# ProPrj_stc8h1k_ESC_2025-05-31.net
KiCad netlist of a schematic drawn in EasyEDA Pro
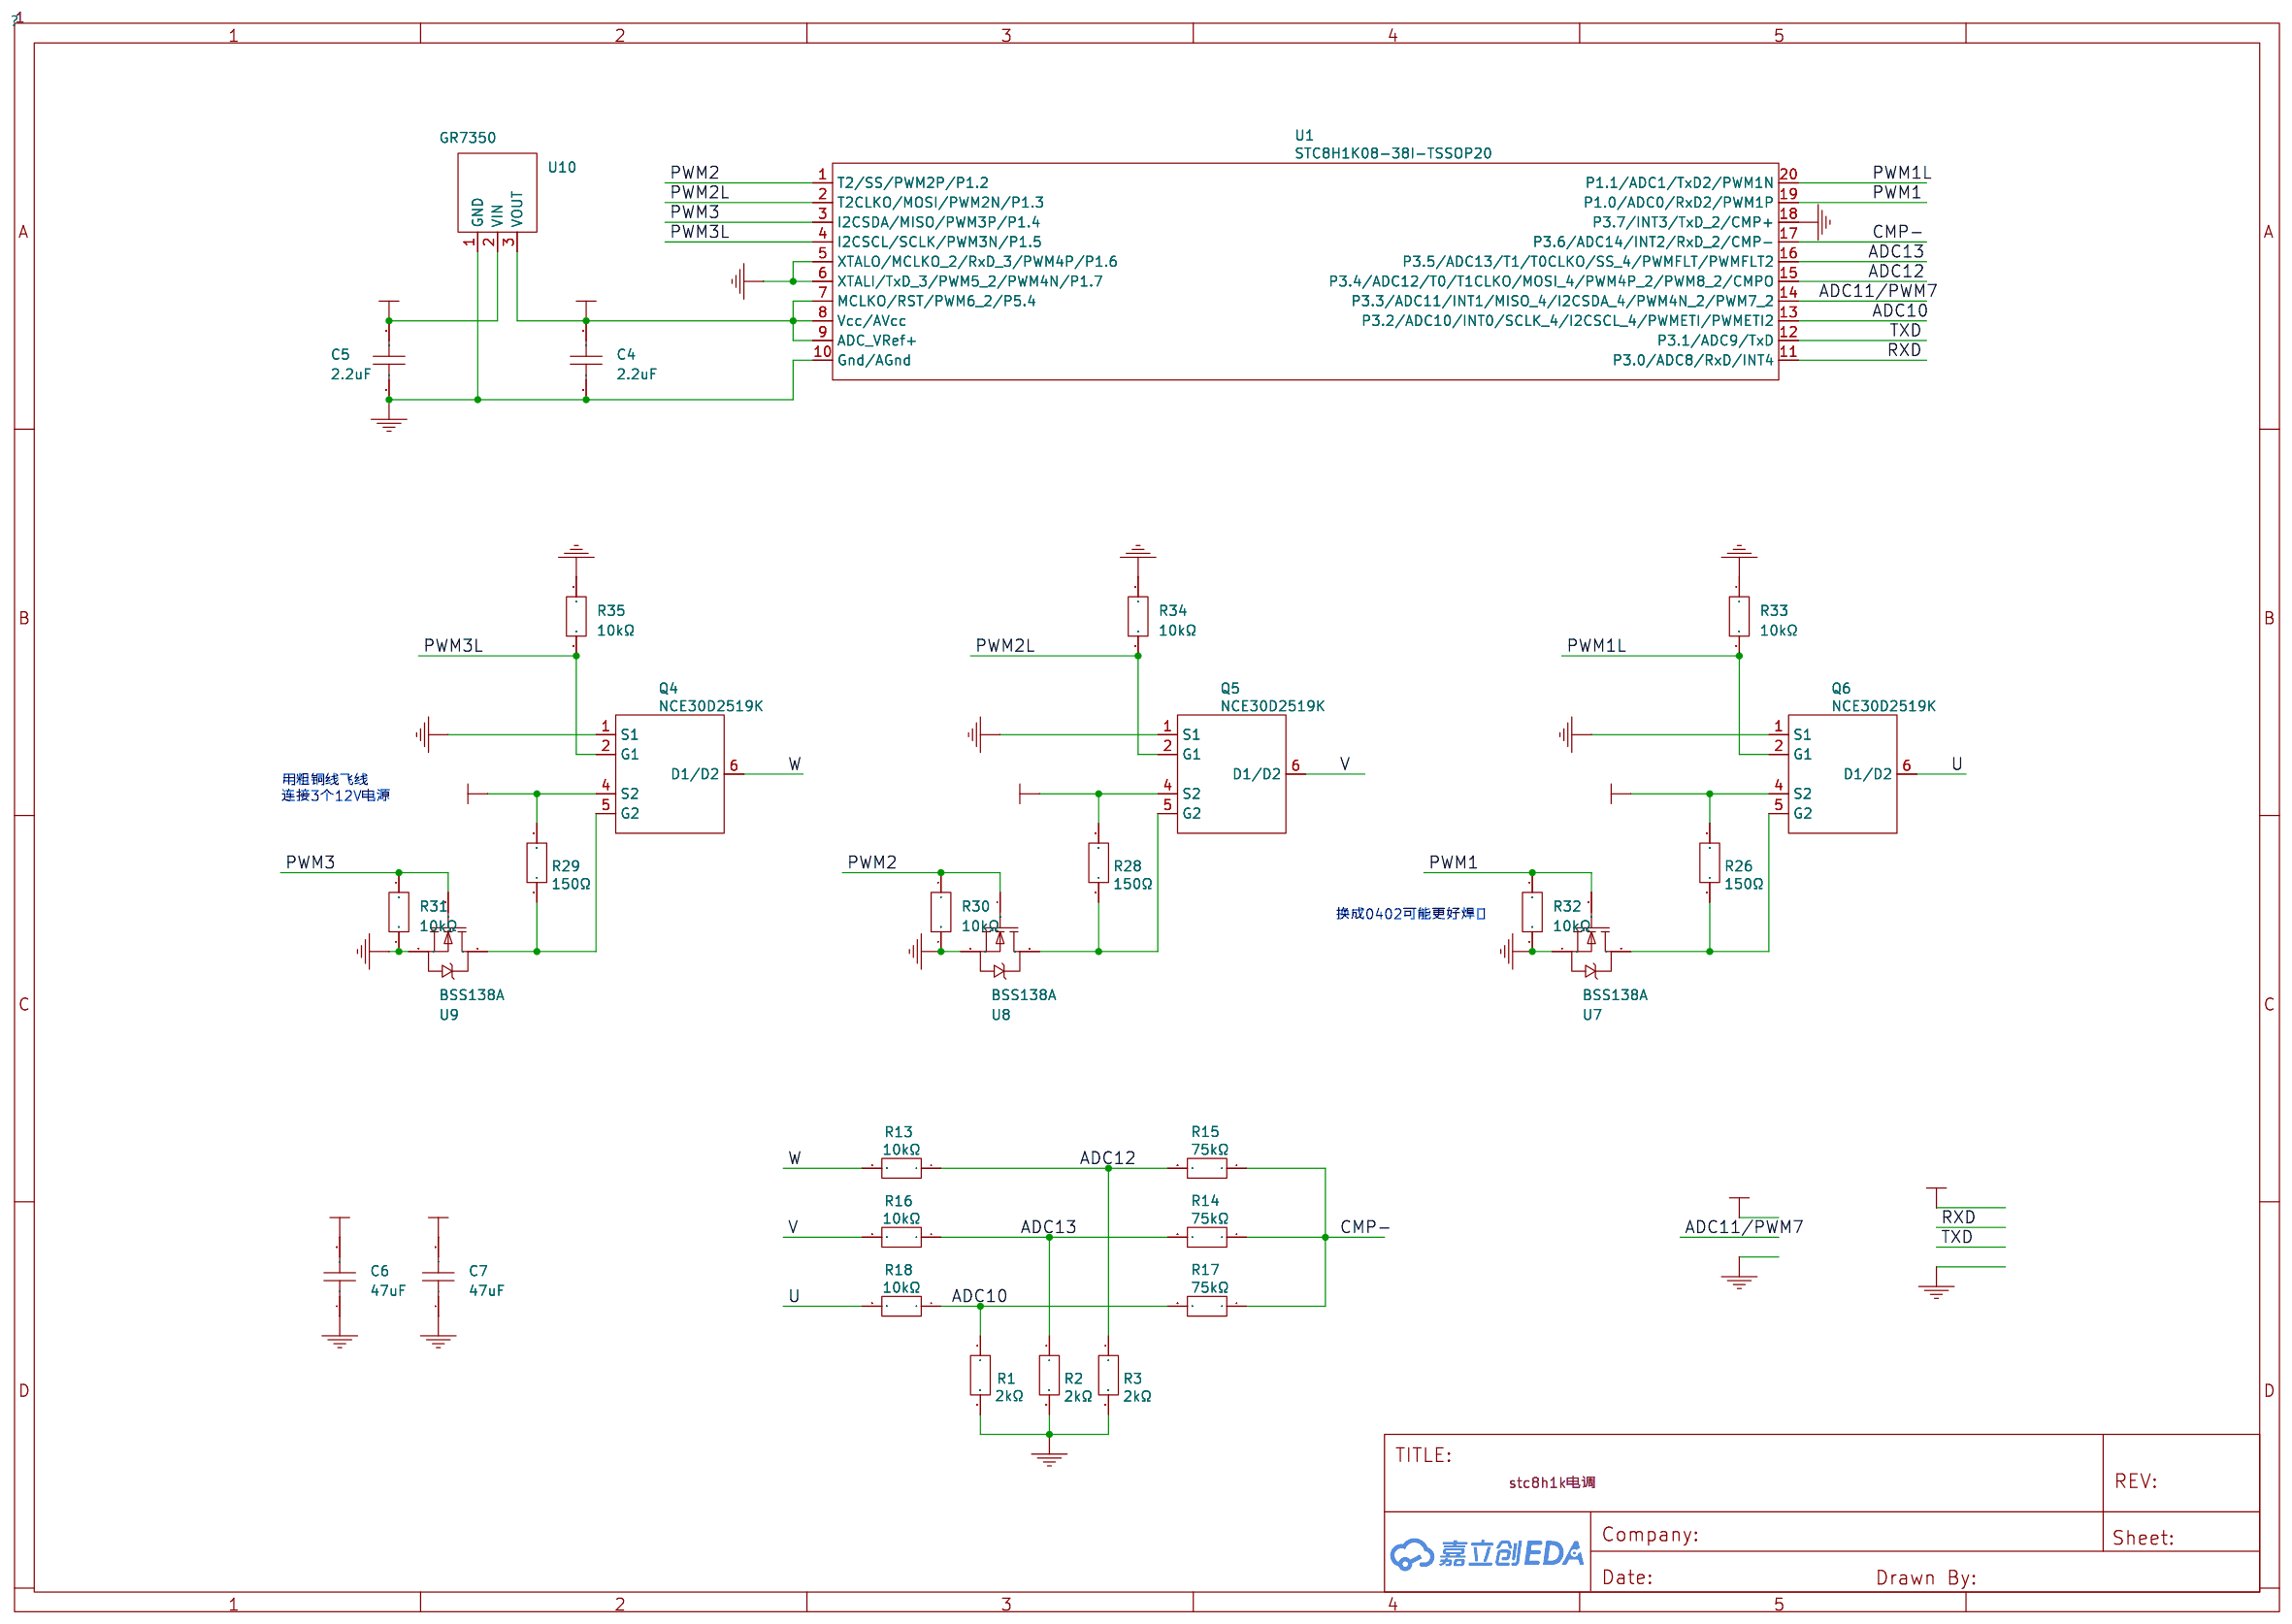
[diagram p0: schematic sheet]

(export (version "E")
  (design (tool "Eeschema 10.0.6"))
  (components
    (comp (ref "C4")
      (value "2.2uF")
      (fields (field (name "Manufacturer Part") "0603B104M250NT") (field (name "Manufacturer") "FH(风华)"))
      (libsource (lib "easyedapro") (part "104"))
    )
    (comp (ref "C5")
      (value "2.2uF")
      (fields (field (name "Manufacturer Part") "0603B104M250NT") (field (name "Manufacturer") "FH(风华)"))
      (libsource (lib "easyedapro") (part "106"))
    )
    (comp (ref "C6")
      (value "47uF")
      (footprint "easyedapro:C1206")
      (description "容值:47uF;精度:±20%;额定电压:25V;材质(温度系数):X5R;")
      (fields
        (field (name "Manufacturer Part") "GRM31CR61E476ME44L")
        (field (name "Manufacturer") "muRata(村田)")
      )
      (libsource (lib "easyedapro") (part "GRM31CR61E476ME44L"))
    )
    (comp (ref "C7")
      (value "47uF")
      (footprint "easyedapro:C1206")
      (description "容值:47uF;精度:±20%;额定电压:25V;材质(温度系数):X5R;")
      (fields
        (field (name "Manufacturer Part") "GRM31CR61E476ME44L")
        (field (name "Manufacturer") "muRata(村田)")
      )
      (libsource (lib "easyedapro") (part "GRM31CR61E476ME44L"))
    )
    (comp (ref "Q4")
      (value "NCE30D2519K")
      (footprint "easyedapro:TO-252-5-11_L6.5-W6.2-P1.14-LS10.0-BR")
      (fields (field (name "Manufacturer") "NCE(无锡新洁能)"))
      (libsource (lib "easyedapro") (part "NCE30D2519K"))
    )
    (comp (ref "Q5")
      (value "NCE30D2519K")
      (footprint "easyedapro:TO-252-5-11_L6.5-W6.2-P1.14-LS10.0-BR")
      (fields (field (name "Manufacturer") "NCE(无锡新洁能)"))
      (libsource (lib "easyedapro") (part "NCE30D2519K"))
    )
    (comp (ref "Q6")
      (value "NCE30D2519K")
      (footprint "easyedapro:TO-252-5-11_L6.5-W6.2-P1.14-LS10.0-BR")
      (fields (field (name "Manufacturer") "NCE(无锡新洁能)"))
      (libsource (lib "easyedapro") (part "NCE30D2519K"))
    )
    (comp (ref "R1")
      (value "2kΩ")
      (fields (field (name "Manufacturer Part") "RC0603FR-1347RL") (field (name "Manufacturer") "YAGEO(国巨)"))
      (libsource (lib "easyedapro") (part "1.5K"))
    )
    (comp (ref "R2")
      (value "2kΩ")
      (fields (field (name "Manufacturer Part") "RC0603FR-1347RL") (field (name "Manufacturer") "YAGEO(国巨)"))
      (libsource (lib "easyedapro") (part "1.5K"))
    )
    (comp (ref "R3")
      (value "2kΩ")
      (fields (field (name "Manufacturer Part") "RC0603FR-1347RL") (field (name "Manufacturer") "YAGEO(国巨)"))
      (libsource (lib "easyedapro") (part "1.5K"))
    )
    (comp (ref "R13")
      (value "10kΩ")
      (fields (field (name "Manufacturer Part") "RC0603FR-1347RL") (field (name "Manufacturer") "YAGEO(国巨)"))
      (libsource (lib "easyedapro") (part "10K"))
    )
    (comp (ref "R14")
      (value "75kΩ")
      (fields (field (name "Manufacturer Part") "RC0603FR-1347RL") (field (name "Manufacturer") "YAGEO(国巨)"))
      (libsource (lib "easyedapro") (part "10K"))
    )
    (comp (ref "R15")
      (value "75kΩ")
      (fields (field (name "Manufacturer Part") "RC0603FR-1347RL") (field (name "Manufacturer") "YAGEO(国巨)"))
      (libsource (lib "easyedapro") (part "10K"))
    )
    (comp (ref "R16")
      (value "10kΩ")
      (fields (field (name "Manufacturer Part") "RC0603FR-1347RL") (field (name "Manufacturer") "YAGEO(国巨)"))
      (libsource (lib "easyedapro") (part "10K"))
    )
    (comp (ref "R17")
      (value "75kΩ")
      (fields (field (name "Manufacturer Part") "RC0603FR-1347RL") (field (name "Manufacturer") "YAGEO(国巨)"))
      (libsource (lib "easyedapro") (part "10K"))
    )
    (comp (ref "R18")
      (value "10kΩ")
      (fields (field (name "Manufacturer Part") "RC0603FR-1347RL") (field (name "Manufacturer") "YAGEO(国巨)"))
      (libsource (lib "easyedapro") (part "10K"))
    )
    (comp (ref "R26")
      (value "150Ω")
      (footprint "easyedapro:R0603")
      (fields (field (name "Manufacturer Part") "RC0603FR-1347RL") (field (name "Manufacturer") "YAGEO(国巨)"))
      (libsource (lib "easyedapro") (part "300R"))
    )
    (comp (ref "R28")
      (value "150Ω")
      (footprint "easyedapro:R0603")
      (fields (field (name "Manufacturer Part") "RC0603FR-1347RL") (field (name "Manufacturer") "YAGEO(国巨)"))
      (libsource (lib "easyedapro") (part "300R"))
    )
    (comp (ref "R29")
      (value "150Ω")
      (footprint "easyedapro:R0603")
      (fields (field (name "Manufacturer Part") "RC0603FR-1347RL") (field (name "Manufacturer") "YAGEO(国巨)"))
      (libsource (lib "easyedapro") (part "300R"))
    )
    (comp (ref "R30")
      (value "10kΩ")
      (fields (field (name "Manufacturer Part") "RC0603FR-1347RL") (field (name "Manufacturer") "YAGEO(国巨)"))
      (libsource (lib "easyedapro") (part "10K"))
    )
    (comp (ref "R31")
      (value "10kΩ")
      (fields (field (name "Manufacturer Part") "RC0603FR-1347RL") (field (name "Manufacturer") "YAGEO(国巨)"))
      (libsource (lib "easyedapro") (part "10K"))
    )
    (comp (ref "R32")
      (value "10kΩ")
      (fields (field (name "Manufacturer Part") "RC0603FR-1347RL") (field (name "Manufacturer") "YAGEO(国巨)"))
      (libsource (lib "easyedapro") (part "10K"))
    )
    (comp (ref "R33")
      (value "10kΩ")
      (fields (field (name "Manufacturer Part") "RC0603FR-1347RL") (field (name "Manufacturer") "YAGEO(国巨)"))
      (libsource (lib "easyedapro") (part "10K"))
    )
    (comp (ref "R34")
      (value "10kΩ")
      (fields (field (name "Manufacturer Part") "RC0603FR-1347RL") (field (name "Manufacturer") "YAGEO(国巨)"))
      (libsource (lib "easyedapro") (part "10K"))
    )
    (comp (ref "R35")
      (value "10kΩ")
      (fields (field (name "Manufacturer Part") "RC0603FR-1347RL") (field (name "Manufacturer") "YAGEO(国巨)"))
      (libsource (lib "easyedapro") (part "10K"))
    )
    (comp (ref "U1")
      (value "STC8H1K08-38I-TSSOP20")
      (libsource (lib "easyedapro") (part "STC8H1K08-38I-TSSOP20"))
    )
    (comp (ref "U7")
      (value "BSS138A")
      (footprint "easyedapro:SOT-23-3_L2.9-W1.6-P1.90-LS2.8-BR")
      (fields (field (name "Manufacturer") "onsemi(安森美)"))
      (libsource (lib "easyedapro") (part "BSS138_C52895"))
    )
    (comp (ref "U8")
      (value "BSS138A")
      (footprint "easyedapro:SOT-23-3_L2.9-W1.6-P1.90-LS2.8-BR")
      (fields (field (name "Manufacturer") "onsemi(安森美)"))
      (libsource (lib "easyedapro") (part "BSS138_C52895"))
    )
    (comp (ref "U9")
      (value "BSS138A")
      (footprint "easyedapro:SOT-23-3_L2.9-W1.6-P1.90-LS2.8-BR")
      (fields (field (name "Manufacturer") "onsemi(安森美)"))
      (libsource (lib "easyedapro") (part "BSS138_C52895"))
    )
    (comp (ref "U10")
      (value "GR7350")
      (footprint "easyedapro:SOT-23-3_L2.9-W1.6-P1.90-LS2.8-BR-CW")
      (description "输出类型:固定;工作电压:36V;输出电压:5V;输出电流:100mA;电源纹波抑制比(PSRR):-;输出极性:正极;")
      (fields (field (name "Manufacturer") "HGSEMI(华冠)"))
      (libsource (lib "easyedapro") (part "HG7550M3-1/TR"))
    )
  )
  (nets
    (net (code "1") (name "/ADC10") (class "Default")
      (node (ref "R1") (pin "1") (pinfunction "1_1") (pintype "unspecified"))
      (node (ref "R17") (pin "2") (pinfunction "2_2") (pintype "unspecified"))
      (node (ref "R18") (pin "1") (pinfunction "1_1") (pintype "unspecified"))
      (node (ref "U1") (pin "13") (pinfunction "P3.2/ADC10/INT0/SCLK_4/I2CSCL_4/PWMETI/PWMETI2_13") (pintype "unspecified"))
    )
    (net (code "2") (name "/ADC11{slash}PWM7") (class "Default")
      (node (ref "U1") (pin "14") (pinfunction "P3.3/ADC11/INT1/MISO_4/I2CSDA_4/PWM4N_2/PWM7_2_14") (pintype "unspecified"))
    )
    (net (code "3") (name "/ADC12") (class "Default")
      (node (ref "R13") (pin "1") (pinfunction "1_1") (pintype "unspecified"))
      (node (ref "R15") (pin "2") (pinfunction "2_2") (pintype "unspecified"))
      (node (ref "R3") (pin "1") (pinfunction "1_1") (pintype "unspecified"))
      (node (ref "U1") (pin "15") (pinfunction "P3.4/ADC12/T0/T1CLKO/MOSI_4/PWM4P_2/PWM8_2/CMPO_15") (pintype "unspecified"))
    )
    (net (code "4") (name "/ADC13") (class "Default")
      (node (ref "R14") (pin "2") (pinfunction "2_2") (pintype "unspecified"))
      (node (ref "R16") (pin "1") (pinfunction "1_1") (pintype "unspecified"))
      (node (ref "R2") (pin "1") (pinfunction "1_1") (pintype "unspecified"))
      (node (ref "U1") (pin "16") (pinfunction "P3.5/ADC13/T1/T0CLKO/SS_4/PWMFLT/PWMFLT2_16") (pintype "unspecified"))
    )
    (net (code "5") (name "/CMP-") (class "Default")
      (node (ref "R14") (pin "1") (pinfunction "1_1") (pintype "unspecified"))
      (node (ref "R15") (pin "1") (pinfunction "1_1") (pintype "unspecified"))
      (node (ref "R17") (pin "1") (pinfunction "1_1") (pintype "unspecified"))
      (node (ref "U1") (pin "17") (pinfunction "P3.6/ADC14/INT2/RxD_2/CMP-_17") (pintype "unspecified"))
    )
    (net (code "6") (name "/PWM1") (class "Default")
      (node (ref "R32") (pin "1") (pinfunction "1_1") (pintype "unspecified"))
      (node (ref "U1") (pin "19") (pinfunction "P1.0/ADC0/RxD2/PWM1P_19") (pintype "unspecified"))
      (node (ref "U7") (pin "1") (pinfunction "G_1") (pintype "input"))
    )
    (net (code "7") (name "/PWM1L") (class "Default")
      (node (ref "Q6") (pin "2") (pinfunction "G1_2") (pintype "unspecified"))
      (node (ref "R33") (pin "2") (pinfunction "2_2") (pintype "unspecified"))
      (node (ref "U1") (pin "20") (pinfunction "P1.1/ADC1/TxD2/PWM1N_20") (pintype "unspecified"))
    )
    (net (code "8") (name "/PWM2") (class "Default")
      (node (ref "R30") (pin "1") (pinfunction "1_1") (pintype "unspecified"))
      (node (ref "U1") (pin "1") (pinfunction "T2/SS/PWM2P/P1.2_1") (pintype "unspecified"))
      (node (ref "U8") (pin "1") (pinfunction "G_1") (pintype "input"))
    )
    (net (code "9") (name "/PWM2L") (class "Default")
      (node (ref "Q5") (pin "2") (pinfunction "G1_2") (pintype "unspecified"))
      (node (ref "R34") (pin "2") (pinfunction "2_2") (pintype "unspecified"))
      (node (ref "U1") (pin "2") (pinfunction "T2CLKO/MOSI/PWM2N/P1.3_2") (pintype "unspecified"))
    )
    (net (code "10") (name "/PWM3") (class "Default")
      (node (ref "R31") (pin "1") (pinfunction "1_1") (pintype "unspecified"))
      (node (ref "U1") (pin "3") (pinfunction "I2CSDA/MISO/PWM3P/P1.4_3") (pintype "unspecified"))
      (node (ref "U9") (pin "1") (pinfunction "G_1") (pintype "input"))
    )
    (net (code "11") (name "/PWM3L") (class "Default")
      (node (ref "Q4") (pin "2") (pinfunction "G1_2") (pintype "unspecified"))
      (node (ref "R35") (pin "2") (pinfunction "2_2") (pintype "unspecified"))
      (node (ref "U1") (pin "4") (pinfunction "I2CSCL/SCLK/PWM3N/P1.5_4") (pintype "unspecified"))
    )
    (net (code "12") (name "/RXD") (class "Default")
      (node (ref "U1") (pin "11") (pinfunction "P3.0/ADC8/RxD/INT4_11") (pintype "unspecified"))
    )
    (net (code "13") (name "/TXD") (class "Default")
      (node (ref "U1") (pin "12") (pinfunction "P3.1/ADC9/TxD_12") (pintype "unspecified"))
    )
    (net (code "14") (name "/U") (class "Default")
      (node (ref "Q6") (pin "6") (pinfunction "D1/D2_6") (pintype "unspecified"))
      (node (ref "R18") (pin "2") (pinfunction "2_2") (pintype "unspecified"))
    )
    (net (code "15") (name "/V") (class "Default")
      (node (ref "Q5") (pin "6") (pinfunction "D1/D2_6") (pintype "unspecified"))
      (node (ref "R16") (pin "2") (pinfunction "2_2") (pintype "unspecified"))
    )
    (net (code "16") (name "/W") (class "Default")
      (node (ref "Q4") (pin "6") (pinfunction "D1/D2_6") (pintype "unspecified"))
      (node (ref "R13") (pin "2") (pinfunction "2_2") (pintype "unspecified"))
    )
    (net (code "17") (name "5V") (class "Default")
      (node (ref "C4") (pin "1") (pinfunction "1_1") (pintype "unspecified"))
      (node (ref "U1") (pin "7") (pinfunction "MCLKO/RST/PWM6_2/P5.4_7") (pintype "unspecified"))
      (node (ref "U1") (pin "8") (pinfunction "Vcc/AVcc_8") (pintype "unspecified"))
      (node (ref "U1") (pin "9") (pinfunction "ADC_VRef+_9") (pintype "unspecified"))
      (node (ref "U10") (pin "3") (pinfunction "VOUT_3") (pintype "unspecified"))
    )
    (net (code "18") (name "12V") (class "Default")
      (node (ref "C5") (pin "2") (pinfunction "2_2") (pintype "unspecified"))
      (node (ref "C6") (pin "2") (pinfunction "2_2") (pintype "unspecified"))
      (node (ref "C7") (pin "2") (pinfunction "2_2") (pintype "unspecified"))
      (node (ref "Q4") (pin "4") (pinfunction "S2_4") (pintype "unspecified"))
      (node (ref "Q5") (pin "4") (pinfunction "S2_4") (pintype "unspecified"))
      (node (ref "Q6") (pin "4") (pinfunction "S2_4") (pintype "unspecified"))
      (node (ref "R26") (pin "2") (pinfunction "2_2") (pintype "unspecified"))
      (node (ref "R28") (pin "2") (pinfunction "2_2") (pintype "unspecified"))
      (node (ref "R29") (pin "2") (pinfunction "2_2") (pintype "unspecified"))
      (node (ref "U10") (pin "2") (pinfunction "VIN_2") (pintype "unspecified"))
    )
    (net (code "19") (name "GND") (class "Default")
      (node (ref "C4") (pin "2") (pinfunction "2_2") (pintype "unspecified"))
      (node (ref "C5") (pin "1") (pinfunction "1_1") (pintype "unspecified"))
      (node (ref "C6") (pin "1") (pinfunction "1_1") (pintype "unspecified"))
      (node (ref "C7") (pin "1") (pinfunction "1_1") (pintype "unspecified"))
      (node (ref "Q4") (pin "1") (pinfunction "S1_1") (pintype "unspecified"))
      (node (ref "Q5") (pin "1") (pinfunction "S1_1") (pintype "unspecified"))
      (node (ref "Q6") (pin "1") (pinfunction "S1_1") (pintype "unspecified"))
      (node (ref "R1") (pin "2") (pinfunction "2_2") (pintype "unspecified"))
      (node (ref "R2") (pin "2") (pinfunction "2_2") (pintype "unspecified"))
      (node (ref "R3") (pin "2") (pinfunction "2_2") (pintype "unspecified"))
      (node (ref "R30") (pin "2") (pinfunction "2_2") (pintype "unspecified"))
      (node (ref "R31") (pin "2") (pinfunction "2_2") (pintype "unspecified"))
      (node (ref "R32") (pin "2") (pinfunction "2_2") (pintype "unspecified"))
      (node (ref "R33") (pin "1") (pinfunction "1_1") (pintype "unspecified"))
      (node (ref "R34") (pin "1") (pinfunction "1_1") (pintype "unspecified"))
      (node (ref "R35") (pin "1") (pinfunction "1_1") (pintype "unspecified"))
      (node (ref "U1") (pin "10") (pinfunction "Gnd/AGnd_10") (pintype "unspecified"))
      (node (ref "U1") (pin "18") (pinfunction "P3.7/INT3/TxD_2/CMP+_18") (pintype "unspecified"))
      (node (ref "U1") (pin "5") (pinfunction "XTALO/MCLKO_2/RxD_3/PWM4P/P1.6_5") (pintype "unspecified"))
      (node (ref "U1") (pin "6") (pinfunction "XTALI/TxD_3/PWM5_2/PWM4N/P1.7_6") (pintype "unspecified"))
      (node (ref "U10") (pin "1") (pinfunction "GND_1") (pintype "unspecified"))
      (node (ref "U7") (pin "2") (pinfunction "S_2") (pintype "input"))
      (node (ref "U8") (pin "2") (pinfunction "S_2") (pintype "input"))
      (node (ref "U9") (pin "2") (pinfunction "S_2") (pintype "input"))
    )
    (net (code "20") (name "Net-(Q4-G2)") (class "Default")
      (node (ref "Q4") (pin "5") (pinfunction "G2_5") (pintype "unspecified"))
      (node (ref "R29") (pin "1") (pinfunction "1_1") (pintype "unspecified"))
      (node (ref "U9") (pin "3") (pinfunction "D_3") (pintype "input"))
    )
    (net (code "21") (name "Net-(Q5-G2)") (class "Default")
      (node (ref "Q5") (pin "5") (pinfunction "G2_5") (pintype "unspecified"))
      (node (ref "R28") (pin "1") (pinfunction "1_1") (pintype "unspecified"))
      (node (ref "U8") (pin "3") (pinfunction "D_3") (pintype "input"))
    )
    (net (code "22") (name "Net-(Q6-G2)") (class "Default")
      (node (ref "Q6") (pin "5") (pinfunction "G2_5") (pintype "unspecified"))
      (node (ref "R26") (pin "1") (pinfunction "1_1") (pintype "unspecified"))
      (node (ref "U7") (pin "3") (pinfunction "D_3") (pintype "input"))
    )
  )
)
